# POWER.net
KiCad netlist of a schematic drawn in Altium Designer
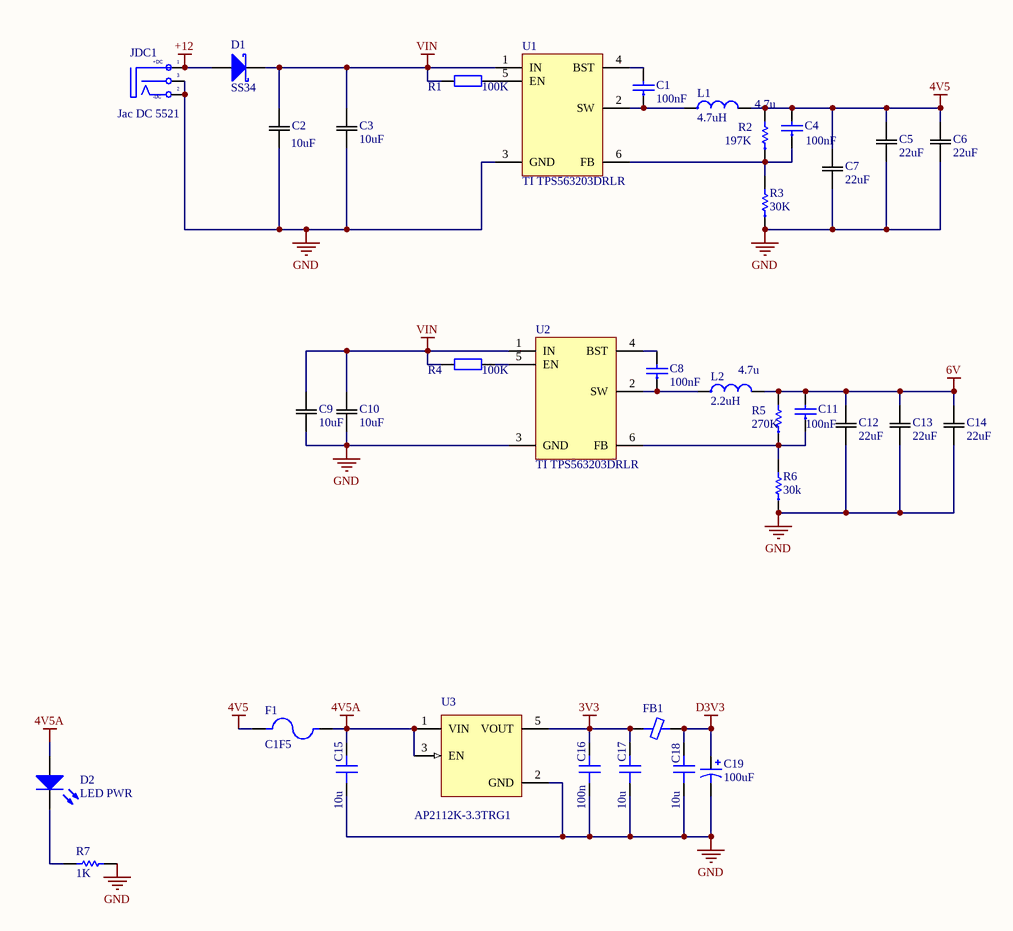
[diagram p0: POWER.SchDoc]

(export (version "E")
  (design (tool "Eeschema 10.0.6"))
  (components
    (comp (ref "C1")
      (value "100nF")
      (footprint "CN-SMD-0603")
      (description "CAP CER 100nF 10% 50V X7R 0603 SMD")
      (libsource (lib "2502-GMQLITE-MAIN") (part "CAPCER0001 100nF 10% 50V X7R 0603 SMD_1"))
    )
    (comp (ref "C2")
      (value "10uF")
      (footprint "CL10A106MQ8NNNC:CAP_CL10_SAM")
      (description "Description")
      (fields
        (field (name "MANUFACTURER_PART_NUMBER") "CL10A106MQ8NNNC")
        (field (name "COPYRIGHT") "Copyright (C) 2026 Ultra Librarian. All rights reserved.")
      )
      (libsource (lib "CL10A106MQ8NNNC") (part "CL10A106MQ8NNNC"))
    )
    (comp (ref "C3")
      (value "10uF")
      (footprint "CL10A106MQ8NNNC:CAP_CL10_SAM")
      (description "Description")
      (fields
        (field (name "MANUFACTURER_PART_NUMBER") "CL10A106MQ8NNNC")
        (field (name "COPYRIGHT") "Copyright (C) 2026 Ultra Librarian. All rights reserved.")
      )
      (libsource (lib "CL10A106MQ8NNNC") (part "CL10A106MQ8NNNC"))
    )
    (comp (ref "C4")
      (value "100nF")
      (footprint "CN-SMD-0603")
      (description "CAP CER 100nF 10% 50V X7R 0603 SMD")
      (libsource (lib "2502-GMQLITE-MAIN") (part "CAPCER0001 100nF 10% 50V X7R 0603 SMD"))
    )
    (comp (ref "C5")
      (value "22uF")
      (footprint "CN-SMD-0603")
      (description "Description")
      (fields
        (field (name "MANUFACTURER_PART_NUMBER") "GRM188R60J226MEA0D")
        (field (name "COPYRIGHT") "Copyright (C) 2026 Ultra Librarian. All rights reserved.")
      )
      (libsource (lib "GRM188R60J226MEA0D") (part "GRM188R60J226MEA0D"))
    )
    (comp (ref "C6")
      (value "22uF")
      (footprint "CN-SMD-0603")
      (description "Description")
      (fields
        (field (name "MANUFACTURER_PART_NUMBER") "GRM188R60J226MEA0D")
        (field (name "COPYRIGHT") "Copyright (C) 2026 Ultra Librarian. All rights reserved.")
      )
      (libsource (lib "GRM188R60J226MEA0D") (part "GRM188R60J226MEA0D"))
    )
    (comp (ref "C7")
      (value "22uF")
      (footprint "CN-SMD-0603")
      (description "Description")
      (fields
        (field (name "MANUFACTURER_PART_NUMBER") "GRM188R60J226MEA0D")
        (field (name "COPYRIGHT") "Copyright (C) 2026 Ultra Librarian. All rights reserved.")
      )
      (libsource (lib "GRM188R60J226MEA0D") (part "GRM188R60J226MEA0D"))
    )
    (comp (ref "C8")
      (value "100nF")
      (footprint "CN-SMD-0603")
      (description "CAP CER 100nF 10% 50V X7R 0603 SMD")
      (libsource (lib "2502-GMQLITE-MAIN") (part "CAPCER0001 100nF 10% 50V X7R 0603 SMD_1"))
    )
    (comp (ref "C9")
      (value "10uF")
      (footprint "CL10A106MQ8NNNC:CAP_CL10_SAM")
      (description "Description")
      (fields
        (field (name "MANUFACTURER_PART_NUMBER") "CL10A106MQ8NNNC")
        (field (name "COPYRIGHT") "Copyright (C) 2026 Ultra Librarian. All rights reserved.")
      )
      (libsource (lib "CL10A106MQ8NNNC") (part "CL10A106MQ8NNNC"))
    )
    (comp (ref "C10")
      (value "10uF")
      (footprint "CL10A106MQ8NNNC:CAP_CL10_SAM")
      (description "Description")
      (fields
        (field (name "MANUFACTURER_PART_NUMBER") "CL10A106MQ8NNNC")
        (field (name "COPYRIGHT") "Copyright (C) 2026 Ultra Librarian. All rights reserved.")
      )
      (libsource (lib "CL10A106MQ8NNNC") (part "CL10A106MQ8NNNC"))
    )
    (comp (ref "C11")
      (value "100nF")
      (footprint "CN-SMD-0603")
      (description "CAP CER 100nF 10% 50V X7R 0603 SMD")
      (libsource (lib "2502-GMQLITE-MAIN") (part "CAPCER0001 100nF 10% 50V X7R 0603 SMD"))
    )
    (comp (ref "C12")
      (value "22uF")
      (footprint "CN-SMD-0603")
      (description "Description")
      (fields
        (field (name "MANUFACTURER_PART_NUMBER") "GRM188R60J226MEA0D")
        (field (name "COPYRIGHT") "Copyright (C) 2026 Ultra Librarian. All rights reserved.")
      )
      (libsource (lib "GRM188R60J226MEA0D") (part "GRM188R60J226MEA0D"))
    )
    (comp (ref "C13")
      (value "22uF")
      (footprint "CN-SMD-0603")
      (description "Description")
      (fields
        (field (name "MANUFACTURER_PART_NUMBER") "GRM188R60J226MEA0D")
        (field (name "COPYRIGHT") "Copyright (C) 2026 Ultra Librarian. All rights reserved.")
      )
      (libsource (lib "GRM188R60J226MEA0D") (part "GRM188R60J226MEA0D"))
    )
    (comp (ref "C14")
      (value "22uF")
      (footprint "CN-SMD-0603")
      (description "Description")
      (fields
        (field (name "MANUFACTURER_PART_NUMBER") "GRM188R60J226MEA0D")
        (field (name "COPYRIGHT") "Copyright (C) 2026 Ultra Librarian. All rights reserved.")
      )
      (libsource (lib "GRM188R60J226MEA0D") (part "GRM188R60J226MEA0D"))
    )
    (comp (ref "C15")
      (value "10u")
      (footprint "CN-SMD-0603")
      (description "CAP0603 X7R 10UF 10% 10V")
      (fields
        (field (name "PART NUMBER") "GMC10X7R106K10NT")
        (field (name "MANUFACTURER") "Cal-Chip Electronics, Inc.")
      )
      (libsource (lib "Celestial Altium Library - altium_library") (part "Capacitor"))
    )
    (comp (ref "C16")
      (value "100n")
      (footprint "CN-SMD-0603")
      (description "CAP0603 X7R 100nF 10% 10V")
      (fields
        (field (name "PART NUMBER") "GMC10X7R106K10NT")
        (field (name "MANUFACTURER") "Cal-Chip Electronics, Inc.")
      )
      (libsource (lib "Celestial Altium Library - altium_library") (part "Capacitor"))
    )
    (comp (ref "C17")
      (value "10u")
      (footprint "CN-SMD-0603")
      (description "CAP0603 X7R 10UF 10% 10V")
      (fields
        (field (name "PART NUMBER") "GMC10X7R106K10NT")
        (field (name "MANUFACTURER") "Cal-Chip Electronics, Inc.")
      )
      (libsource (lib "Celestial Altium Library - altium_library") (part "Capacitor"))
    )
    (comp (ref "C18")
      (value "10u")
      (footprint "CN-SMD-0603")
      (description "CAP0603 X7R 10UF 10% 10V")
      (fields
        (field (name "PART NUMBER") "GMC10X7R106K10NT")
        (field (name "MANUFACTURER") "Cal-Chip Electronics, Inc.")
      )
      (libsource (lib "Celestial Altium Library - altium_library") (part "Capacitor"))
    )
    (comp (ref "C19")
      (value "100uF")
      (footprint "CAP-ALU-SMD-5.5x5.5")
      (description "CAP ALUM 100UF 20% \r\n16V SMD")
      (fields (field (name "Comment") "CAP ALUM 100UF 20% 16V SMD"))
      (libsource (lib "capacitor") (part "UWT1C101MCL1GB"))
    )
    (comp (ref "D1")
      (value "SS34")
      (footprint "DIO-SMD-106")
      (description "Schottky Diode 40V 3A SMA")
      (libsource (lib "diode") (part "SS34"))
    )
    (comp (ref "D2")
      (value "LED PWR")
      (footprint "LED-0805-Red")
      (description "Lite-On LED Red 0603")
      (fields (field (name "Comment") "LED Red"))
      (libsource (lib "diode") (part "LTST-C190KRKT"))
    )
    (comp (ref "F1")
      (value "C1F5")
      (footprint "RES-SMD-1206")
      (description "Fuse Chip Fast Acting 5A 125V SMD Solder Pad 1206 3.2 X 1.58 X 0.63mm")
      (fields (field (name "MANUFACTURER") "Bel TRP"))
      (libsource (lib "POWER_PIN_CAMERA") (part "C1F5"))
    )
    (comp (ref "FB1")
      (value "330")
      (footprint "IND_BLM18KG331WH1D_MUR-L")
      (description "FERRITE BEAD 330 OHM 0603 1LN")
      (fields
        (field (name "PART NUMBER") "BLM18KG331SH1D")
        (field (name "MANUFACTURER") "Murata Electronics")
      )
      (libsource (lib "Celestial Altium Library - altium_library") (part "Ferrite Chip"))
    )
    (comp (ref "JDC1")
      (value "Jac DC 5521")
      (footprint "DC0")
      (description "Jac DC input")
      (libsource (lib "2502-GMQLITE-MAIN") (part "DCIN"))
    )
    (comp (ref "L1")
      (value "4.7uH")
      (footprint "Inductor_SMD")
      (description "IND MOI 1W2T 4.7uH 20% 5A 0420 SMD")
      (fields (field (name "ALTIUM_VALUE") "4.7u"))
      (libsource (lib "2502-GMQLITE-MAIN") (part "INDMOI0016 1W2T 2.2uH 20% 5A 0420 SMD"))
    )
    (comp (ref "L2")
      (value "2.2uH")
      (footprint "Inductor_SMD")
      (description "IND MOI 1W2T 4.7uH 20% 5A 0420 SMD")
      (fields (field (name "ALTIUM_VALUE") "4.7u"))
      (libsource (lib "2502-GMQLITE-MAIN") (part "INDMOI0016 1W2T 2.2uH 20% 5A 0420 SMD"))
    )
    (comp (ref "R1")
      (value "100K")
      (footprint "RES-SMD-0603")
      (description "Yageo RES 100K 5% 1/10W 0603")
      (fields (field (name "Comment") "RES 100K 5% 1/10W 0603"))
      (libsource (lib "resistor") (part "RC0603JR-07100KL"))
    )
    (comp (ref "R2")
      (value "197K")
      (footprint "RES-SMD-0603")
      (description "RES CHP 2K7 1% 1/10W 0603 SMD")
      (libsource (lib "2502-GMQLITE-MAIN") (part "RESCHP0195 2K7 1% 0603 SMD"))
    )
    (comp (ref "R3")
      (value "30K")
      (footprint "RES-SMD-0603")
      (description "RES CHP 2K7 1% 1/10W 0603 SMD")
      (libsource (lib "2502-GMQLITE-MAIN") (part "RESCHP0195 2K7 1% 0603 SMD"))
    )
    (comp (ref "R4")
      (value "100K")
      (footprint "RES-SMD-0603")
      (description "Yageo RES 100K 5% 1/10W 0603")
      (fields (field (name "Comment") "RES 100K 5% 1/10W 0603"))
      (libsource (lib "resistor") (part "RC0603JR-07100KL"))
    )
    (comp (ref "R5")
      (value "270K")
      (footprint "RES-SMD-0603")
      (description "RES CHP 2K7 1% 1/10W 0603 SMD")
      (libsource (lib "2502-GMQLITE-MAIN") (part "RESCHP0195 2K7 1% 0603 SMD"))
    )
    (comp (ref "R6")
      (value "30k")
      (footprint "RES-SMD-0603")
      (description "RES CHP 2K7 1% 1/10W 0603 SMD")
      (libsource (lib "2502-GMQLITE-MAIN") (part "RESCHP0195 2K7 1% 0603 SMD"))
    )
    (comp (ref "R7")
      (value "1K")
      (footprint "RES-SMD-0603")
      (description "Res Thick Film 0603 2.2K Ohm 5% 1/10W ±200ppm/°C Molded SMD SMD Paper T/R")
      (fields
        (field (name "MANUFACTURER") "Vishay")
        (field (name "MANUFACTURER PART NUMBER") "CRCW06032K20JNEA")
      )
      (libsource (lib "Stm32_Flyback_Driver_250814_1") (part "Resistor 2.2K"))
    )
    (comp (ref "U1")
      (value "TI TPS563203DRLR")
      (footprint "SOT50P160X60-6N:SOT50P160X60-6N")
      (description "ICS OCV BCK TPS563201 3A SOT23-6 SMD")
      (libsource (lib "2502-GMQLITE-MAIN") (part "ICSOCV0021 BCK TPS563201 3A SOT23-6 SMD"))
    )
    (comp (ref "U2")
      (value "TI TPS563203DRLR")
      (footprint "SOT50P160X60-6N:SOT50P160X60-6N")
      (description "ICS OCV BCK TPS563201 3A SOT23-6 SMD")
      (libsource (lib "2502-GMQLITE-MAIN") (part "ICSOCV0021 BCK TPS563201 3A SOT23-6 SMD"))
    )
    (comp (ref "U3")
      (value "AP2112K-3.3TRG1")
      (footprint "AP2112K-3P3TRG1:SOT_RG1_DIO")
      (description "AP2112 Series 0.6 A 3.3 V Fixed Output SMT LDO Linear Regulator - SOT23-5")
      (fields (field (name "MF") "Diodes Inc."))
      (libsource (lib "hanguyen") (part "AP2112K-3.3TRG1"))
    )
  )
  (nets
    (net (code "1") (name "+12") (class "Default")
      (node (ref "D1") (pin "1") (pinfunction "A_1") (pintype "passive"))
      (node (ref "JDC1") (pin "1") (pinfunction "T_1") (pintype "passive"))
    )
    (net (code "2") (name "3V3") (class "Default")
      (node (ref "C16") (pin "2") (pinfunction "2_2") (pintype "passive"))
      (node (ref "C17") (pin "2") (pinfunction "2_2") (pintype "passive"))
      (node (ref "FB1") (pin "1") (pinfunction "1_1") (pintype "passive"))
      (node (ref "U3") (pin "5") (pinfunction "VOUT_5") (pintype "power_in"))
    )
    (net (code "3") (name "4V5") (class "Default")
      (node (ref "C4") (pin "2") (pinfunction "2_2") (pintype "passive"))
      (node (ref "C5") (pin "2") (pinfunction "2_2") (pintype "passive"))
      (node (ref "C6") (pin "2") (pinfunction "2_2") (pintype "passive"))
      (node (ref "C7") (pin "2") (pinfunction "2_2") (pintype "passive"))
      (node (ref "F1") (pin "1") (pinfunction "1_1") (pintype "passive"))
      (node (ref "L1") (pin "2") (pinfunction "2_2") (pintype "passive"))
      (node (ref "R2") (pin "2") (pinfunction "2_2") (pintype "passive"))
    )
    (net (code "4") (name "4V5A") (class "Default")
      (node (ref "C15") (pin "2") (pinfunction "2_2") (pintype "passive"))
      (node (ref "D2") (pin "1") (pinfunction "A_1") (pintype "passive"))
      (node (ref "F1") (pin "2") (pinfunction "2_2") (pintype "passive"))
      (node (ref "U3") (pin "1") (pinfunction "VIN_1") (pintype "power_in"))
      (node (ref "U3") (pin "3") (pinfunction "EN_3") (pintype "input"))
    )
    (net (code "5") (name "6V") (class "Default")
      (node (ref "C11") (pin "2") (pinfunction "2_2") (pintype "passive"))
      (node (ref "C12") (pin "2") (pinfunction "2_2") (pintype "passive"))
      (node (ref "C13") (pin "2") (pinfunction "2_2") (pintype "passive"))
      (node (ref "C14") (pin "2") (pinfunction "2_2") (pintype "passive"))
      (node (ref "L2") (pin "2") (pinfunction "2_2") (pintype "passive"))
      (node (ref "R5") (pin "2") (pinfunction "2_2") (pintype "passive"))
    )
    (net (code "6") (name "D3V3") (class "Default")
      (node (ref "C18") (pin "2") (pinfunction "2_2") (pintype "passive"))
      (node (ref "C19") (pin "1") (pinfunction "1_1") (pintype "passive"))
      (node (ref "FB1") (pin "2") (pinfunction "2_2") (pintype "passive"))
    )
    (net (code "7") (name "GND") (class "Default")
      (node (ref "C10") (pin "1") (pinfunction "1_1") (pintype "passive"))
      (node (ref "C12") (pin "1") (pinfunction "1_1") (pintype "passive"))
      (node (ref "C13") (pin "1") (pinfunction "1_1") (pintype "passive"))
      (node (ref "C14") (pin "1") (pinfunction "1_1") (pintype "passive"))
      (node (ref "C15") (pin "1") (pinfunction "1_1") (pintype "passive"))
      (node (ref "C16") (pin "1") (pinfunction "1_1") (pintype "passive"))
      (node (ref "C17") (pin "1") (pinfunction "1_1") (pintype "passive"))
      (node (ref "C18") (pin "1") (pinfunction "1_1") (pintype "passive"))
      (node (ref "C19") (pin "2") (pinfunction "2_2") (pintype "passive"))
      (node (ref "C2") (pin "1") (pinfunction "1_1") (pintype "passive"))
      (node (ref "C3") (pin "1") (pinfunction "1_1") (pintype "passive"))
      (node (ref "C5") (pin "1") (pinfunction "1_1") (pintype "passive"))
      (node (ref "C6") (pin "1") (pinfunction "1_1") (pintype "passive"))
      (node (ref "C7") (pin "1") (pinfunction "1_1") (pintype "passive"))
      (node (ref "C9") (pin "1") (pinfunction "1_1") (pintype "passive"))
      (node (ref "JDC1") (pin "2") (pinfunction "TN_2") (pintype "passive"))
      (node (ref "JDC1") (pin "3") (pinfunction "S_3") (pintype "power_in"))
      (node (ref "R3") (pin "1") (pinfunction "1_1") (pintype "passive"))
      (node (ref "R6") (pin "1") (pinfunction "1_1") (pintype "passive"))
      (node (ref "R7") (pin "2") (pinfunction "2_2") (pintype "passive"))
      (node (ref "U1") (pin "3") (pinfunction "GND_3") (pintype "power_in"))
      (node (ref "U2") (pin "3") (pinfunction "GND_3") (pintype "power_in"))
      (node (ref "U3") (pin "2") (pinfunction "GND_2") (pintype "power_in"))
    )
    (net (code "8") (name "Net-(D2-K)") (class "Default")
      (node (ref "D2") (pin "2") (pinfunction "K_2") (pintype "passive"))
      (node (ref "R7") (pin "1") (pinfunction "1_1") (pintype "passive"))
    )
    (net (code "9") (name "Net-(U1-BST)") (class "Default")
      (node (ref "C1") (pin "2") (pinfunction "2_2") (pintype "passive"))
      (node (ref "U1") (pin "4") (pinfunction "BST_4") (pintype "passive"))
    )
    (net (code "10") (name "Net-(U1-EN)") (class "Default")
      (node (ref "R1") (pin "1") (pinfunction "1_1") (pintype "passive"))
      (node (ref "U1") (pin "5") (pinfunction "EN_5") (pintype "passive"))
    )
    (net (code "11") (name "Net-(U1-FB)") (class "Default")
      (node (ref "C4") (pin "1") (pinfunction "1_1") (pintype "passive"))
      (node (ref "R2") (pin "1") (pinfunction "1_1") (pintype "passive"))
      (node (ref "R3") (pin "2") (pinfunction "2_2") (pintype "passive"))
      (node (ref "U1") (pin "6") (pinfunction "FB_6") (pintype "passive"))
    )
    (net (code "12") (name "Net-(U1-SW)") (class "Default")
      (node (ref "C1") (pin "1") (pinfunction "1_1") (pintype "passive"))
      (node (ref "L1") (pin "1") (pinfunction "1_1") (pintype "passive"))
      (node (ref "U1") (pin "2") (pinfunction "SW_2") (pintype "passive"))
    )
    (net (code "13") (name "Net-(U2-BST)") (class "Default")
      (node (ref "C8") (pin "2") (pinfunction "2_2") (pintype "passive"))
      (node (ref "U2") (pin "4") (pinfunction "BST_4") (pintype "passive"))
    )
    (net (code "14") (name "Net-(U2-EN)") (class "Default")
      (node (ref "R4") (pin "1") (pinfunction "1_1") (pintype "passive"))
      (node (ref "U2") (pin "5") (pinfunction "EN_5") (pintype "passive"))
    )
    (net (code "15") (name "Net-(U2-FB)") (class "Default")
      (node (ref "C11") (pin "1") (pinfunction "1_1") (pintype "passive"))
      (node (ref "R5") (pin "1") (pinfunction "1_1") (pintype "passive"))
      (node (ref "R6") (pin "2") (pinfunction "2_2") (pintype "passive"))
      (node (ref "U2") (pin "6") (pinfunction "FB_6") (pintype "passive"))
    )
    (net (code "16") (name "Net-(U2-SW)") (class "Default")
      (node (ref "C8") (pin "1") (pinfunction "1_1") (pintype "passive"))
      (node (ref "L2") (pin "1") (pinfunction "1_1") (pintype "passive"))
      (node (ref "U2") (pin "2") (pinfunction "SW_2") (pintype "passive"))
    )
    (net (code "17") (name "VIN") (class "Default")
      (node (ref "C10") (pin "2") (pinfunction "2_2") (pintype "passive"))
      (node (ref "C2") (pin "2") (pinfunction "2_2") (pintype "passive"))
      (node (ref "C3") (pin "2") (pinfunction "2_2") (pintype "passive"))
      (node (ref "C9") (pin "2") (pinfunction "2_2") (pintype "passive"))
      (node (ref "D1") (pin "2") (pinfunction "K_2") (pintype "passive"))
      (node (ref "R1") (pin "2") (pinfunction "2_2") (pintype "passive"))
      (node (ref "R4") (pin "2") (pinfunction "2_2") (pintype "passive"))
      (node (ref "U1") (pin "1") (pinfunction "IN_1") (pintype "power_in"))
      (node (ref "U2") (pin "1") (pinfunction "IN_1") (pintype "power_in"))
    )
  )
)
